# LB-word-MCU.net
KiCad netlist of a schematic drawn in Altium Designer
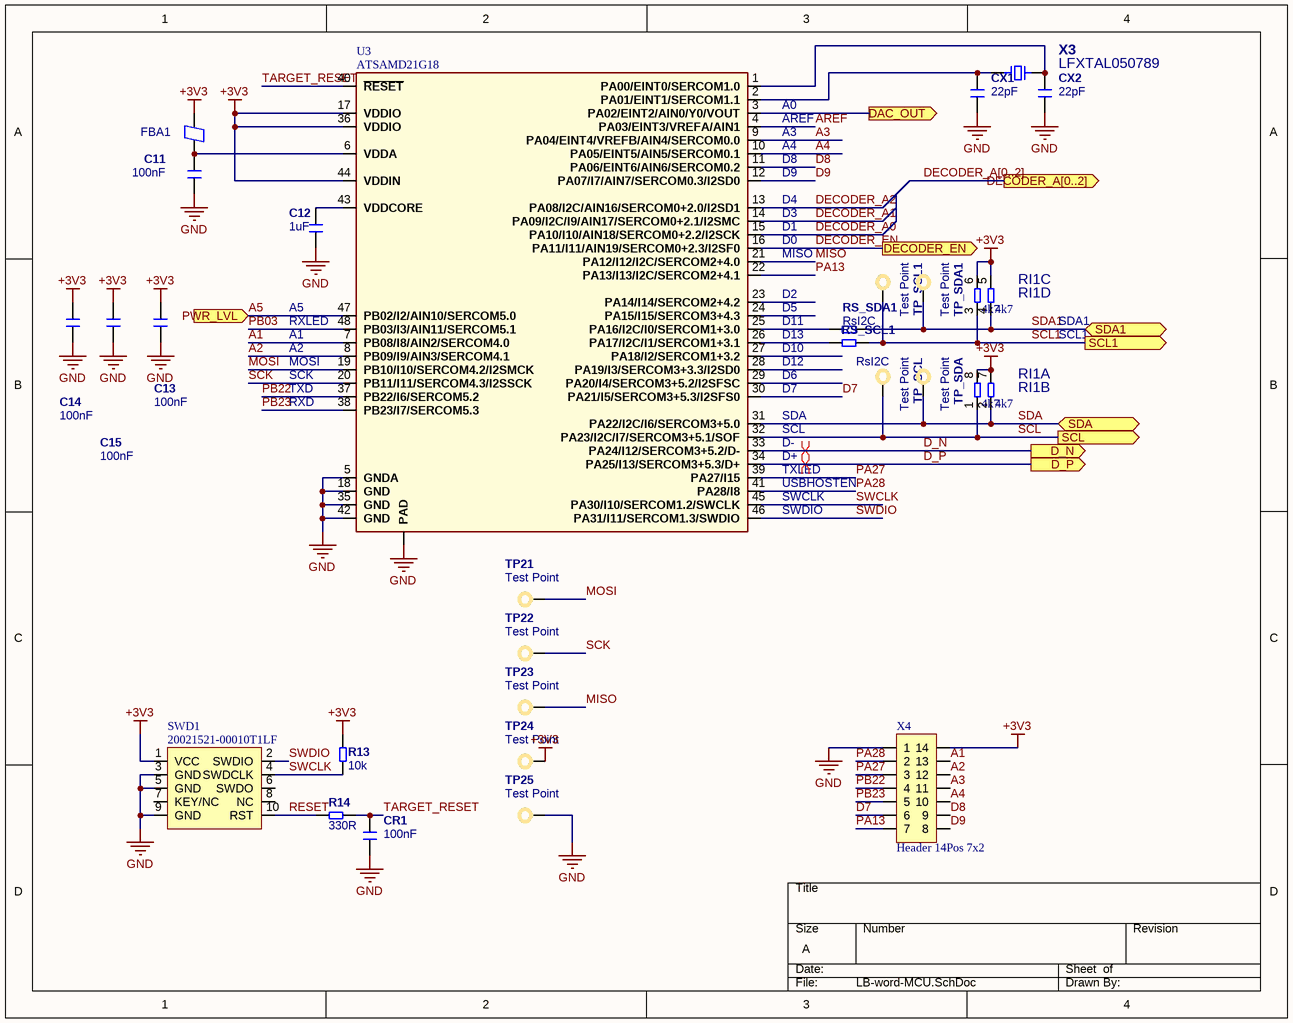
[diagram p0: LB-word-MCU.SchDoc]

(export (version "E")
  (design (tool "Eeschema 10.0.6"))
  (components
    (comp (ref "C11")
      (value "100nF")
      (footprint "C0603_N")
      (description "Capacitor MLCC")
      (fields
        (field (name "MANUFACTURER") "Yageo")
        (field (name "MANUFACTURER PART NUMBER") "CC0603KRX7R9BB104")
      )
      (libsource (lib "wes") (part "Capacitor"))
    )
    (comp (ref "C12")
      (value "1uF")
      (footprint "C0603_N")
      (description "Capacitor MLCC")
      (fields
        (field (name "MANUFACTURER") "Yageo")
        (field (name "MANUFACTURER PART NUMBER") "CC0603KRX7R9BB104")
      )
      (libsource (lib "wes") (part "Capacitor"))
    )
    (comp (ref "C13")
      (value "100nF")
      (footprint "C0603_N")
      (description "Capacitor MLCC")
      (fields
        (field (name "MANUFACTURER") "Yageo")
        (field (name "MANUFACTURER PART NUMBER") "CC0603KRX7R9BB104")
      )
      (libsource (lib "wes") (part "Capacitor"))
    )
    (comp (ref "C14")
      (value "100nF")
      (footprint "C0603_N")
      (description "Capacitor MLCC")
      (fields
        (field (name "MANUFACTURER") "Yageo")
        (field (name "MANUFACTURER PART NUMBER") "CC0603KRX7R9BB104")
      )
      (libsource (lib "wes") (part "Capacitor"))
    )
    (comp (ref "C15")
      (value "100nF")
      (footprint "C0603_N")
      (description "Capacitor MLCC")
      (fields
        (field (name "MANUFACTURER") "Yageo")
        (field (name "MANUFACTURER PART NUMBER") "CC0603KRX7R9BB104")
      )
      (libsource (lib "wes") (part "Capacitor"))
    )
    (comp (ref "CR1")
      (value "100nF")
      (footprint "C0603_N")
      (description "Capacitor MLCC")
      (fields
        (field (name "MANUFACTURER") "Yageo")
        (field (name "MANUFACTURER PART NUMBER") "CC0603KRX7R9BB104")
      )
      (libsource (lib "wes") (part "Capacitor"))
    )
    (comp (ref "CX1")
      (value "22pF")
      (footprint "C0603_N")
      (description "Capacitor MLCC")
      (fields
        (field (name "MANUFACTURER") "Yageo")
        (field (name "MANUFACTURER PART NUMBER") "CC0603KRX7R9BB104")
      )
      (libsource (lib "wes") (part "Capacitor"))
    )
    (comp (ref "CX2")
      (value "22pF")
      (footprint "C0603_N")
      (description "Capacitor MLCC")
      (fields
        (field (name "MANUFACTURER") "Yageo")
        (field (name "MANUFACTURER PART NUMBER") "CC0603KRX7R9BB104")
      )
      (libsource (lib "wes") (part "Capacitor"))
    )
    (comp (ref "FBA1") (value "FB") (footprint "F0603_N") (libsource (lib "wes") (part "Ferrite Bead")))
    (comp (ref "R13")
      (value "10k")
      (footprint "R0603")
      (fields (field (name "PUBLISHER") "Altium Limited"))
      (libsource (lib "wes") (part "Resistor"))
    )
    (comp (ref "R14")
      (value "330R")
      (footprint "R0603")
      (fields (field (name "PUBLISHER") "Altium Limited"))
      (libsource (lib "wes") (part "Resistor"))
    )
    (comp (ref "RI1")
      (value "4k7")
      (footprint "YC164")
      (fields (field (name "Comment") "; 4k7"))
      (libsource (lib "wes") (part "Resistor Array - 4P"))
    )
    (comp (ref "RS_SCL1")
      (value "RsI2C")
      (footprint "R0603")
      (fields (field (name "PUBLISHER") "Altium Limited"))
      (libsource (lib "wes") (part "Resistor"))
    )
    (comp (ref "RS_SDA1")
      (value "RsI2C")
      (footprint "R0603")
      (fields (field (name "PUBLISHER") "Altium Limited"))
      (libsource (lib "wes") (part "Resistor"))
    )
    (comp (ref "SWD1")
      (value "20021521-00010T1LF")
      (footprint "Header 10P 50mil")
      (libsource (lib "wes") (part "SWD"))
    )
    (comp (ref "TP21")
      (value "Test Point")
      (footprint "TestPoint-1.2mm")
      (libsource (lib "wes") (part "Test Point"))
    )
    (comp (ref "TP22")
      (value "Test Point")
      (footprint "TestPoint-1.2mm")
      (libsource (lib "wes") (part "Test Point"))
    )
    (comp (ref "TP23")
      (value "Test Point")
      (footprint "TestPoint-1.2mm")
      (libsource (lib "wes") (part "Test Point"))
    )
    (comp (ref "TP24")
      (value "Test Point")
      (footprint "TestPoint-1.2mm")
      (libsource (lib "wes") (part "Test Point"))
    )
    (comp (ref "TP25")
      (value "Test Point")
      (footprint "TestPoint-1.2mm")
      (libsource (lib "wes") (part "Test Point"))
    )
    (comp (ref "TP_SCL")
      (value "Test Point")
      (footprint "TestPoint-1.2mm")
      (libsource (lib "wes") (part "Test Point"))
    )
    (comp (ref "TP_SCL1")
      (value "Test Point")
      (footprint "TestPoint-1.2mm")
      (libsource (lib "wes") (part "Test Point"))
    )
    (comp (ref "TP_SDA")
      (value "Test Point")
      (footprint "TestPoint-1.2mm")
      (libsource (lib "wes") (part "Test Point"))
    )
    (comp (ref "TP_SDA1")
      (value "Test Point")
      (footprint "TestPoint-1.2mm")
      (libsource (lib "wes") (part "Test Point"))
    )
    (comp (ref "U3") (value "ATSAMD21G18") (footprint "QFN48_M") (libsource (lib "wes") (part "ATSAMD21G18")))
    (comp (ref "X3")
      (value "LFXTAL050789")
      (footprint "Crystal 0805")
      (libsource (lib "wes") (part "Crystal"))
    )
    (comp (ref "X4")
      (value "Header 14Pos 7x2")
      (footprint "Header 7x2 SMD 2.54mm")
      (libsource (lib "wes") (part "Header 14Pos 7x2"))
    )
  )
  (nets
    (net (code "1") (name "+3V3") (class "Default")
      (node (ref "C13") (pin "1") (pintype "passive"))
      (node (ref "C14") (pin "1") (pintype "passive"))
      (node (ref "C15") (pin "1") (pintype "passive"))
      (node (ref "FBA1") (pin "2") (pinfunction "2_2") (pintype "passive"))
      (node (ref "R13") (pin "2") (pinfunction "2_2") (pintype "passive"))
      (node (ref "RI1") (pin "5") (pinfunction "5_5") (pintype "passive"))
      (node (ref "RI1") (pin "6") (pinfunction "6_6") (pintype "passive"))
      (node (ref "RI1") (pin "7") (pinfunction "7_7") (pintype "passive"))
      (node (ref "RI1") (pin "8") (pinfunction "8_8") (pintype "passive"))
      (node (ref "SWD1") (pin "1") (pinfunction "VCC_1") (pintype "power_in"))
      (node (ref "TP24") (pin "1") (pinfunction "1_1") (pintype "passive"))
      (node (ref "U3") (pin "17") (pinfunction "VDDIO_17") (pintype "power_in"))
      (node (ref "U3") (pin "36") (pinfunction "VDDIO_36") (pintype "power_in"))
      (node (ref "U3") (pin "44") (pinfunction "VDDIN_44") (pintype "power_in"))
      (node (ref "X4") (pin "14") (pinfunction "14_14") (pintype "power_in"))
    )
    (net (code "2") (name "/A1") (class "Default")
      (node (ref "U3") (pin "7") (pinfunction "PB08/I8/AIN2/SERCOM4.0_7") (pintype "passive"))
      (node (ref "X4") (pin "13") (pinfunction "13_13") (pintype "power_in"))
    )
    (net (code "3") (name "/A2") (class "Default")
      (node (ref "U3") (pin "8") (pinfunction "PB09/I9/AIN3/SERCOM4.1_8") (pintype "passive"))
      (node (ref "X4") (pin "12") (pinfunction "12_12") (pintype "power_in"))
    )
    (net (code "4") (name "/A3") (class "Default")
      (node (ref "U3") (pin "9") (pinfunction "PA04/EINT4/VREFB/AIN4/SERCOM0.0_9") (pintype "passive"))
      (node (ref "X4") (pin "11") (pinfunction "11_11") (pintype "power_in"))
    )
    (net (code "5") (name "/A4") (class "Default")
      (node (ref "U3") (pin "10") (pinfunction "PA05/EINT5/AIN5/SERCOM0.1_10") (pintype "passive"))
      (node (ref "X4") (pin "10") (pinfunction "10_10") (pintype "power_in"))
    )
    (net (code "6") (name "/A5") (class "Default")
      (node (ref "U3") (pin "47") (pinfunction "PB02/I2/AIN10/SERCOM5.0_47") (pintype "passive"))
    )
    (net (code "7") (name "/AREF") (class "Default")
      (node (ref "U3") (pin "4") (pinfunction "PA03/EINT3/VREFA/AIN1_4") (pintype "passive"))
    )
    (net (code "8") (name "/D7") (class "Default")
      (node (ref "U3") (pin "30") (pinfunction "PA21/I5/SERCOM3+5.3/I2SFS0_30") (pintype "passive"))
      (node (ref "X4") (pin "6") (pinfunction "6_6") (pintype "power_in"))
    )
    (net (code "9") (name "/D8") (class "Default")
      (node (ref "U3") (pin "11") (pinfunction "PA06/EINT6/AIN6/SERCOM0.2_11") (pintype "passive"))
      (node (ref "X4") (pin "9") (pinfunction "9_9") (pintype "power_in"))
    )
    (net (code "10") (name "/D9") (class "Default")
      (node (ref "U3") (pin "12") (pinfunction "PA07/I7/AIN7/SERCOM0.3/I2SD0_12") (pintype "passive"))
      (node (ref "X4") (pin "8") (pinfunction "8_8") (pintype "power_in"))
    )
    (net (code "11") (name "/DAC_OUT") (class "Default")
      (node (ref "U3") (pin "3") (pinfunction "PA02/EINT2/AIN0/Y0/VOUT_3") (pintype "passive"))
    )
    (net (code "12") (name "/DECODER_A0") (class "Default")
      (node (ref "U3") (pin "15") (pinfunction "PA10/I10/AIN18/SERCOM0+2.2/I2SCK_15") (pintype "passive"))
    )
    (net (code "13") (name "/DECODER_A1") (class "Default")
      (node (ref "U3") (pin "14") (pinfunction "PA09/I2C/I9/AIN17/SERCOM0+2.1/I2SMC_14") (pintype "passive"))
    )
    (net (code "14") (name "/DECODER_A2") (class "Default")
      (node (ref "U3") (pin "13") (pinfunction "PA08/I2C/AIN16/SERCOM0+2.0/I2SD1_13") (pintype "passive"))
    )
    (net (code "16") (name "/DECODER_EN") (class "Default")
      (node (ref "U3") (pin "16") (pinfunction "PA11/I11/AIN19/SERCOM0+2.3/I2SF0_16") (pintype "passive"))
    )
    (net (code "17") (name "/D_N") (class "Default")
      (node (ref "U3") (pin "33") (pinfunction "PA24/I12/SERCOM3+5.2/D-_33") (pintype "passive"))
    )
    (net (code "18") (name "/D_P") (class "Default")
      (node (ref "U3") (pin "34") (pinfunction "PA25/I13/SERCOM3+5.3/D+_34") (pintype "passive"))
    )
    (net (code "19") (name "/MISO") (class "Default")
      (node (ref "TP23") (pin "1") (pinfunction "1_1") (pintype "passive"))
      (node (ref "U3") (pin "21") (pinfunction "PA12/I12/I2C/SERCOM2+4.0_21") (pintype "passive"))
    )
    (net (code "20") (name "/MOSI") (class "Default")
      (node (ref "TP21") (pin "1") (pinfunction "1_1") (pintype "passive"))
      (node (ref "U3") (pin "19") (pinfunction "PB10/I10/SERCOM4.2/I2SMCK_19") (pintype "passive"))
    )
    (net (code "21") (name "/PA13") (class "Default")
      (node (ref "U3") (pin "22") (pinfunction "PA13/I13/I2C/SERCOM2+4.1_22") (pintype "passive"))
      (node (ref "X4") (pin "7") (pinfunction "7_7") (pintype "power_in"))
    )
    (net (code "22") (name "/PA27") (class "Default")
      (node (ref "U3") (pin "39") (pinfunction "PA27/I15_39") (pintype "passive"))
      (node (ref "X4") (pin "3") (pinfunction "3_3") (pintype "power_in"))
    )
    (net (code "23") (name "/PA28") (class "Default")
      (node (ref "U3") (pin "41") (pinfunction "PA28/I8_41") (pintype "passive"))
      (node (ref "X4") (pin "2") (pinfunction "2_2") (pintype "power_in"))
    )
    (net (code "24") (name "/PB03") (class "Default")
      (node (ref "U3") (pin "48") (pinfunction "PB03/I3/AIN11/SERCOM5.1_48") (pintype "passive"))
    )
    (net (code "25") (name "/PB22") (class "Default")
      (node (ref "U3") (pin "37") (pinfunction "PB22/I6/SERCOM5.2_37") (pintype "passive"))
      (node (ref "X4") (pin "4") (pinfunction "4_4") (pintype "power_in"))
    )
    (net (code "26") (name "/PB23") (class "Default")
      (node (ref "U3") (pin "38") (pinfunction "PB23/I7/SERCOM5.3_38") (pintype "passive"))
      (node (ref "X4") (pin "5") (pinfunction "5_5") (pintype "power_in"))
    )
    (net (code "27") (name "/RESET") (class "Default")
      (node (ref "R14") (pin "1") (pinfunction "1_1") (pintype "passive"))
      (node (ref "SWD1") (pin "10") (pinfunction "RST_10") (pintype "power_in"))
    )
    (net (code "28") (name "/SCK") (class "Default")
      (node (ref "TP22") (pin "1") (pinfunction "1_1") (pintype "passive"))
      (node (ref "U3") (pin "20") (pinfunction "PB11/I11/SERCOM4.3/I2SSCK_20") (pintype "passive"))
    )
    (net (code "29") (name "/SCL") (class "Default")
      (node (ref "RI1") (pin "1") (pinfunction "1_1") (pintype "passive"))
      (node (ref "TP_SCL") (pin "1") (pinfunction "1_1") (pintype "passive"))
      (node (ref "U3") (pin "32") (pinfunction "PA23/I2C/I7/SERCOM3+5.1/SOF_32") (pintype "passive"))
    )
    (net (code "30") (name "/SCL1") (class "Default")
      (node (ref "RI1") (pin "3") (pinfunction "3_3") (pintype "passive"))
      (node (ref "RS_SCL1") (pin "2") (pinfunction "2_2") (pintype "passive"))
      (node (ref "TP_SCL1") (pin "1") (pinfunction "1_1") (pintype "passive"))
    )
    (net (code "31") (name "/SDA") (class "Default")
      (node (ref "RI1") (pin "2") (pinfunction "2_2") (pintype "passive"))
      (node (ref "TP_SDA") (pin "1") (pinfunction "1_1") (pintype "passive"))
      (node (ref "U3") (pin "31") (pinfunction "PA22/I2C/I6/SERCOM3+5.0_31") (pintype "passive"))
    )
    (net (code "32") (name "/SDA1") (class "Default")
      (node (ref "RI1") (pin "4") (pinfunction "4_4") (pintype "passive"))
      (node (ref "RS_SDA1") (pin "2") (pinfunction "2_2") (pintype "passive"))
      (node (ref "TP_SDA1") (pin "1") (pinfunction "1_1") (pintype "passive"))
    )
    (net (code "33") (name "/SWCLK") (class "Default")
      (node (ref "R13") (pin "1") (pinfunction "1_1") (pintype "passive"))
      (node (ref "SWD1") (pin "4") (pinfunction "SWDCLK_4") (pintype "power_in"))
      (node (ref "U3") (pin "45") (pinfunction "PA30/I10/SERCOM1.2/SWCLK_45") (pintype "passive"))
    )
    (net (code "34") (name "/SWDIO") (class "Default")
      (node (ref "SWD1") (pin "2") (pinfunction "SWDIO_2") (pintype "power_in"))
      (node (ref "U3") (pin "46") (pinfunction "PA31/I11/SERCOM1.3/SWDIO_46") (pintype "passive"))
    )
    (net (code "35") (name "/TARGET_RESET") (class "Default")
      (node (ref "CR1") (pin "1") (pintype "passive"))
      (node (ref "R14") (pin "2") (pinfunction "2_2") (pintype "passive"))
      (node (ref "U3") (pin "40") (pinfunction "~{RESET}_40") (pintype "passive"))
    )
    (net (code "36") (name "GND") (class "Default")
      (node (ref "C11") (pin "2") (pintype "passive"))
      (node (ref "C12") (pin "2") (pintype "passive"))
      (node (ref "C13") (pin "2") (pintype "passive"))
      (node (ref "C14") (pin "2") (pintype "passive"))
      (node (ref "C15") (pin "2") (pintype "passive"))
      (node (ref "CR1") (pin "2") (pintype "passive"))
      (node (ref "CX1") (pin "2") (pintype "passive"))
      (node (ref "CX2") (pin "2") (pintype "passive"))
      (node (ref "SWD1") (pin "3") (pinfunction "GND_3") (pintype "power_in"))
      (node (ref "SWD1") (pin "5") (pinfunction "GND_5") (pintype "power_in"))
      (node (ref "SWD1") (pin "9") (pinfunction "GND_9") (pintype "power_in"))
      (node (ref "TP25") (pin "1") (pinfunction "1_1") (pintype "passive"))
      (node (ref "U3") (pin "18") (pinfunction "GND_18") (pintype "power_in"))
      (node (ref "U3") (pin "35") (pinfunction "GND_35") (pintype "power_in"))
      (node (ref "U3") (pin "42") (pinfunction "GND_42") (pintype "power_in"))
      (node (ref "U3") (pin "49") (pinfunction "PAD_49") (pintype "power_in"))
      (node (ref "U3") (pin "5") (pinfunction "GNDA_5") (pintype "power_in"))
      (node (ref "X4") (pin "1") (pinfunction "1_1") (pintype "power_in"))
    )
    (net (code "37") (name "Net-(U3-PA00{slash}EINT0{slash}SERCOM1.0)") (class "Default")
      (node (ref "CX2") (pin "1") (pintype "passive"))
      (node (ref "U3") (pin "1") (pinfunction "PA00/EINT0/SERCOM1.0_1") (pintype "passive"))
      (node (ref "X3") (pin "2") (pinfunction "2_2") (pintype "passive"))
    )
    (net (code "38") (name "Net-(U3-PA01{slash}EINT1{slash}SERCOM1.1)") (class "Default")
      (node (ref "CX1") (pin "1") (pintype "passive"))
      (node (ref "U3") (pin "2") (pinfunction "PA01/EINT1/SERCOM1.1_2") (pintype "passive"))
      (node (ref "X3") (pin "1") (pinfunction "1_1") (pintype "passive"))
    )
    (net (code "39") (name "Net-(U3-PA16{slash}I2C{slash}I0{slash}SERCOM1+3.0)") (class "Default")
      (node (ref "RS_SDA1") (pin "1") (pinfunction "1_1") (pintype "passive"))
      (node (ref "U3") (pin "25") (pinfunction "PA16/I2C/I0/SERCOM1+3.0_25") (pintype "passive"))
    )
    (net (code "40") (name "Net-(U3-PA17{slash}I2C{slash}I1{slash}SERCOM1+3.1)") (class "Default")
      (node (ref "RS_SCL1") (pin "1") (pinfunction "1_1") (pintype "passive"))
      (node (ref "U3") (pin "26") (pinfunction "PA17/I2C/I1/SERCOM1+3.1_26") (pintype "passive"))
    )
    (net (code "41") (name "Net-(U3-VDDA)") (class "Default")
      (node (ref "C11") (pin "1") (pintype "passive"))
      (node (ref "FBA1") (pin "1") (pinfunction "1_1") (pintype "passive"))
      (node (ref "U3") (pin "6") (pinfunction "VDDA_6") (pintype "power_in"))
    )
    (net (code "42") (name "Net-(U3-VDDCORE)") (class "Default")
      (node (ref "C12") (pin "1") (pintype "passive"))
      (node (ref "U3") (pin "43") (pinfunction "VDDCORE_43") (pintype "power_in"))
    )
    (net (code "43") (name "unconnected-(SWD1-KEY{slash}NC-Pad7)") (class "Default")
      (node (ref "SWD1") (pin "7") (pinfunction "KEY/NC_7") (pintype "power_in"))
    )
    (net (code "44") (name "unconnected-(SWD1-NC-Pad8)") (class "Default")
      (node (ref "SWD1") (pin "8") (pinfunction "NC_8") (pintype "power_in"))
    )
    (net (code "45") (name "unconnected-(SWD1-SWDO-Pad6)") (class "Default")
      (node (ref "SWD1") (pin "6") (pinfunction "SWDO_6") (pintype "power_in"))
    )
    (net (code "46") (name "unconnected-(U3-PA14{slash}I14{slash}SERCOM2+4.2-Pad23)") (class "Default")
      (node (ref "U3") (pin "23") (pinfunction "PA14/I14/SERCOM2+4.2_23") (pintype "passive"))
    )
    (net (code "47") (name "unconnected-(U3-PA15{slash}I15{slash}SERCOM3+4.3-Pad24)") (class "Default")
      (node (ref "U3") (pin "24") (pinfunction "PA15/I15/SERCOM3+4.3_24") (pintype "passive"))
    )
    (net (code "48") (name "unconnected-(U3-PA18{slash}I2{slash}SERCOM1+3.2-Pad27)") (class "Default")
      (node (ref "U3") (pin "27") (pinfunction "PA18/I2/SERCOM1+3.2_27") (pintype "passive"))
    )
    (net (code "49") (name "unconnected-(U3-PA19{slash}I3{slash}SERCOM3+3.3{slash}I2SD0-Pad28)") (class "Default")
      (node (ref "U3") (pin "28") (pinfunction "PA19/I3/SERCOM3+3.3/I2SD0_28") (pintype "passive"))
    )
    (net (code "50") (name "unconnected-(U3-PA20{slash}I4{slash}SERCOM3+5.2{slash}I2SFSC-Pad29)") (class "Default")
      (node (ref "U3") (pin "29") (pinfunction "PA20/I4/SERCOM3+5.2/I2SFSC_29") (pintype "passive"))
    )
  )
)
